# Node_Hub.net
KiCad netlist of a schematic drawn in Altium Designer
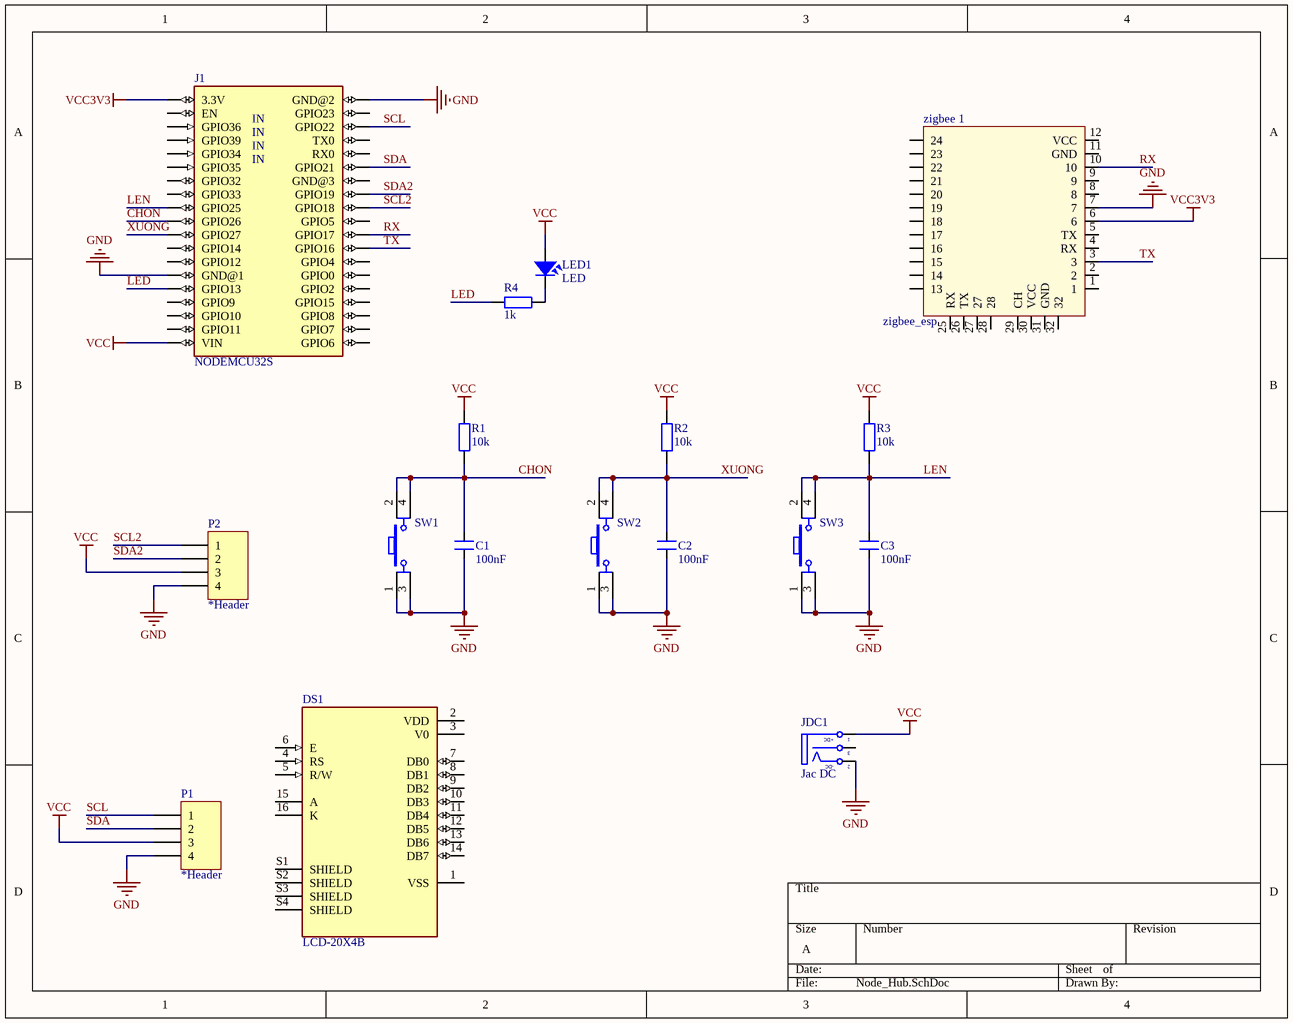
[diagram p0: Node_Hub.SchDoc]

(export (version "E")
  (design (tool "Eeschema 10.0.6"))
  (components
    (comp (ref "C1")
      (value "100nF")
      (footprint "CN1")
      (description "Cremic For Xtal 1pF => 100pF")
      (libsource (lib "syhaunguyen") (part "CN0"))
    )
    (comp (ref "C2")
      (value "100nF")
      (footprint "CN1")
      (description "Cremic For Xtal 1pF => 100pF")
      (libsource (lib "syhaunguyen") (part "CN0"))
    )
    (comp (ref "C3")
      (value "100nF")
      (footprint "CN1")
      (description "Cremic For Xtal 1pF => 100pF")
      (libsource (lib "syhaunguyen") (part "CN0"))
    )
    (comp (ref "DS1")
      (value "LCD-20X4B")
      (footprint "LCD_LCD-20X4B")
      (description "Display Development Tools 20X4 CHARACTER BLUE LCD W/BACKLIGHT")
      (fields (field (name "MF") "Gravitech"))
      (libsource (lib "LCD-20X4B") (part "LCD-20X4B"))
    )
    (comp (ref "J1")
      (value "NODEMCU32S")
      (footprint "NODEMCU32S")
      (description "WIFI MODULE V1")
      (fields (field (name "MF") "AI-Thinker") (field (name "MP") "NODEMCU-32S"))
      (libsource (lib "NODEMCU32S") (part "NODEMCU32S"))
    )
    (comp (ref "JDC1")
      (value "Jac DC")
      (footprint "DC-IN")
      (description "Jac DC input")
      (libsource (lib "syhaunguyen") (part "DCIN"))
    )
    (comp (ref "LED1")
      (value "LED")
      (footprint "LED-3")
      (description "LED Single colour Green and Red")
      (libsource (lib "syhaunguyen") (part "LED"))
    )
    (comp (ref "P1")
      (value "*Header")
      (footprint "HDR1X4")
      (description "Header, 4-Pin, Right Angle")
      (fields (field (name "PUBLISHER") "Altium Limited"))
      (libsource (lib "Cty1") (part "Header 4"))
    )
    (comp (ref "P2")
      (value "*Header")
      (footprint "HDR1X4")
      (description "Header, 4-Pin, Right Angle")
      (fields (field (name "PUBLISHER") "Altium Limited"))
      (libsource (lib "Cty1") (part "Header 4"))
    )
    (comp (ref "R1")
      (value "10k")
      (footprint "R1/4W")
      (description "Resistor 1/4W")
      (libsource (lib "syhaunguyen") (part "R1/4W"))
    )
    (comp (ref "R2")
      (value "10k")
      (footprint "R1/4W")
      (description "Resistor 1/4W")
      (libsource (lib "syhaunguyen") (part "R1/4W"))
    )
    (comp (ref "R3")
      (value "10k")
      (footprint "R1/4W")
      (description "Resistor 1/4W")
      (libsource (lib "syhaunguyen") (part "R1/4W"))
    )
    (comp (ref "R4")
      (value "1k")
      (footprint "R1/4W")
      (description "Resistor 1/4W")
      (libsource (lib "syhaunguyen") (part "R1/4W"))
    )
    (comp (ref "SW1")
      (value "SW")
      (footprint "SW4")
      (description "Switch button 4 pin")
      (libsource (lib "syhaunguyen") (part "SW4"))
    )
    (comp (ref "SW2")
      (value "SW")
      (footprint "SW4")
      (description "Switch button 4 pin")
      (libsource (lib "syhaunguyen") (part "SW4"))
    )
    (comp (ref "SW3")
      (value "SW")
      (footprint "SW4")
      (description "Switch button 4 pin")
      (libsource (lib "syhaunguyen") (part "SW4"))
    )
    (comp (ref "zigbee 1")
      (value "zigbee_esp")
      (footprint "zigbee")
      (libsource (lib "Main_stm8") (part "zigbee_esp"))
    )
  )
  (nets
    (net (code "2") (name "/CHON") (class "Default")
      (node (ref "C1") (pin "2") (pinfunction "2_2") (pintype "passive"))
      (node (ref "J1") (pin "GPIO26") (pinfunction "GPIO26_GPIO26") (pintype "bidirectional"))
      (node (ref "R1") (pin "1") (pinfunction "1_1") (pintype "passive"))
      (node (ref "SW1") (pin "2") (pintype "passive"))
      (node (ref "SW1") (pin "4") (pintype "passive"))
    )
    (net (code "3") (name "/LED") (class "Default")
      (node (ref "J1") (pin "GPIO13") (pinfunction "GPIO13_GPIO13") (pintype "bidirectional"))
      (node (ref "R4") (pin "1") (pinfunction "1_1") (pintype "passive"))
    )
    (net (code "4") (name "/LEN") (class "Default")
      (node (ref "C3") (pin "2") (pinfunction "2_2") (pintype "passive"))
      (node (ref "J1") (pin "GPIO25") (pinfunction "GPIO25_GPIO25") (pintype "bidirectional"))
      (node (ref "R3") (pin "1") (pinfunction "1_1") (pintype "passive"))
      (node (ref "SW3") (pin "2") (pintype "passive"))
      (node (ref "SW3") (pin "4") (pintype "passive"))
    )
    (net (code "5") (name "/RX") (class "Default")
      (node (ref "J1") (pin "GPIO17") (pinfunction "GPIO17_GPIO17") (pintype "bidirectional"))
      (node (ref "zigbee 1") (pin "10") (pinfunction "10_10") (pintype "passive"))
    )
    (net (code "6") (name "/SCL") (class "Default")
      (node (ref "J1") (pin "GPIO22") (pinfunction "GPIO22_GPIO22") (pintype "bidirectional"))
      (node (ref "P1") (pin "1") (pinfunction "1_1") (pintype "passive"))
    )
    (net (code "7") (name "/SCL2") (class "Default")
      (node (ref "J1") (pin "GPIO18") (pinfunction "GPIO18_GPIO18") (pintype "bidirectional"))
      (node (ref "P2") (pin "1") (pinfunction "1_1") (pintype "passive"))
    )
    (net (code "8") (name "/SDA") (class "Default")
      (node (ref "J1") (pin "GPIO21") (pinfunction "GPIO21_GPIO21") (pintype "bidirectional"))
      (node (ref "P1") (pin "2") (pinfunction "2_2") (pintype "passive"))
    )
    (net (code "9") (name "/SDA2") (class "Default")
      (node (ref "J1") (pin "GPIO19") (pinfunction "GPIO19_GPIO19") (pintype "bidirectional"))
      (node (ref "P2") (pin "2") (pinfunction "2_2") (pintype "passive"))
    )
    (net (code "10") (name "/TX") (class "Default")
      (node (ref "J1") (pin "GPIO16") (pinfunction "GPIO16_GPIO16") (pintype "bidirectional"))
      (node (ref "zigbee 1") (pin "3") (pinfunction "3_3") (pintype "passive"))
    )
    (net (code "11") (name "/XUONG") (class "Default")
      (node (ref "C2") (pin "2") (pinfunction "2_2") (pintype "passive"))
      (node (ref "J1") (pin "GPIO27") (pinfunction "GPIO27_GPIO27") (pintype "bidirectional"))
      (node (ref "R2") (pin "1") (pinfunction "1_1") (pintype "passive"))
      (node (ref "SW2") (pin "2") (pintype "passive"))
      (node (ref "SW2") (pin "4") (pintype "passive"))
    )
    (net (code "12") (name "GND") (class "Default")
      (node (ref "C1") (pin "1") (pinfunction "1_1") (pintype "passive"))
      (node (ref "C2") (pin "1") (pinfunction "1_1") (pintype "passive"))
      (node (ref "C3") (pin "1") (pinfunction "1_1") (pintype "passive"))
      (node (ref "J1") (pin "GND@1") (pinfunction "GND@1_GND@1") (pintype "bidirectional"))
      (node (ref "J1") (pin "GND@2") (pinfunction "GND@2_GND@2") (pintype "bidirectional"))
      (node (ref "JDC1") (pin "2") (pinfunction "TN_2") (pintype "passive"))
      (node (ref "P1") (pin "4") (pinfunction "4_4") (pintype "passive"))
      (node (ref "P2") (pin "4") (pinfunction "4_4") (pintype "passive"))
      (node (ref "SW1") (pin "1") (pintype "passive"))
      (node (ref "SW1") (pin "3") (pintype "passive"))
      (node (ref "SW2") (pin "1") (pintype "passive"))
      (node (ref "SW2") (pin "3") (pintype "passive"))
      (node (ref "SW3") (pin "1") (pintype "passive"))
      (node (ref "SW3") (pin "3") (pintype "passive"))
      (node (ref "zigbee 1") (pin "7") (pinfunction "7_7") (pintype "passive"))
    )
    (net (code "13") (name "Net-(LED1-Pad2)") (class "Default")
      (node (ref "LED1") (pin "2") (pinfunction "2_2") (pintype "passive"))
      (node (ref "R4") (pin "2") (pinfunction "2_2") (pintype "passive"))
    )
    (net (code "14") (name "VCC") (class "Default")
      (node (ref "J1") (pin "VIN") (pinfunction "VIN_VIN") (pintype "bidirectional"))
      (node (ref "JDC1") (pin "1") (pinfunction "T_1") (pintype "passive"))
      (node (ref "LED1") (pin "1") (pinfunction "1_1") (pintype "passive"))
      (node (ref "P1") (pin "3") (pinfunction "3_3") (pintype "passive"))
      (node (ref "P2") (pin "3") (pinfunction "3_3") (pintype "passive"))
      (node (ref "R1") (pin "2") (pinfunction "2_2") (pintype "passive"))
      (node (ref "R2") (pin "2") (pinfunction "2_2") (pintype "passive"))
      (node (ref "R3") (pin "2") (pinfunction "2_2") (pintype "passive"))
    )
    (net (code "15") (name "VCC3V3") (class "Default")
      (node (ref "J1") (pin "3V3") (pinfunction "3.3V_3V3") (pintype "bidirectional"))
      (node (ref "zigbee 1") (pin "6") (pinfunction "6_6") (pintype "passive"))
    )
    (net (code "16") (name "unconnected-(DS1-A-Pad15)") (class "Default")
      (node (ref "DS1") (pin "15") (pinfunction "A_15") (pintype "passive"))
    )
    (net (code "17") (name "unconnected-(DS1-DB0-Pad7)") (class "Default")
      (node (ref "DS1") (pin "7") (pinfunction "DB0_7") (pintype "bidirectional"))
    )
    (net (code "18") (name "unconnected-(DS1-DB1-Pad8)") (class "Default")
      (node (ref "DS1") (pin "8") (pinfunction "DB1_8") (pintype "bidirectional"))
    )
    (net (code "19") (name "unconnected-(DS1-DB2-Pad9)") (class "Default")
      (node (ref "DS1") (pin "9") (pinfunction "DB2_9") (pintype "bidirectional"))
    )
    (net (code "20") (name "unconnected-(DS1-DB3-Pad10)") (class "Default")
      (node (ref "DS1") (pin "10") (pinfunction "DB3_10") (pintype "bidirectional"))
    )
    (net (code "21") (name "unconnected-(DS1-DB4-Pad11)") (class "Default")
      (node (ref "DS1") (pin "11") (pinfunction "DB4_11") (pintype "bidirectional"))
    )
    (net (code "22") (name "unconnected-(DS1-DB5-Pad12)") (class "Default")
      (node (ref "DS1") (pin "12") (pinfunction "DB5_12") (pintype "bidirectional"))
    )
    (net (code "23") (name "unconnected-(DS1-DB6-Pad13)") (class "Default")
      (node (ref "DS1") (pin "13") (pinfunction "DB6_13") (pintype "bidirectional"))
    )
    (net (code "24") (name "unconnected-(DS1-DB7-Pad14)") (class "Default")
      (node (ref "DS1") (pin "14") (pinfunction "DB7_14") (pintype "bidirectional"))
    )
    (net (code "25") (name "unconnected-(DS1-E-Pad6)") (class "Default")
      (node (ref "DS1") (pin "6") (pinfunction "E_6") (pintype "input"))
    )
    (net (code "26") (name "unconnected-(DS1-K-Pad16)") (class "Default")
      (node (ref "DS1") (pin "16") (pinfunction "K_16") (pintype "passive"))
    )
    (net (code "27") (name "unconnected-(DS1-RS-Pad4)") (class "Default")
      (node (ref "DS1") (pin "4") (pinfunction "RS_4") (pintype "input"))
    )
    (net (code "28") (name "unconnected-(DS1-R{slash}W-Pad5)") (class "Default")
      (node (ref "DS1") (pin "5") (pinfunction "R/W_5") (pintype "input"))
    )
    (net (code "29") (name "unconnected-(DS1-SHIELD-PadS1)") (class "Default")
      (node (ref "DS1") (pin "S1") (pinfunction "SHIELD_S1") (pintype "passive"))
    )
    (net (code "30") (name "unconnected-(DS1-SHIELD-PadS2)") (class "Default")
      (node (ref "DS1") (pin "S2") (pinfunction "SHIELD_S2") (pintype "passive"))
    )
    (net (code "31") (name "unconnected-(DS1-SHIELD-PadS3)") (class "Default")
      (node (ref "DS1") (pin "S3") (pinfunction "SHIELD_S3") (pintype "passive"))
    )
    (net (code "32") (name "unconnected-(DS1-SHIELD-PadS4)") (class "Default")
      (node (ref "DS1") (pin "S4") (pinfunction "SHIELD_S4") (pintype "passive"))
    )
    (net (code "33") (name "unconnected-(DS1-V0-Pad3)") (class "Default")
      (node (ref "DS1") (pin "3") (pinfunction "V0_3") (pintype "power_in"))
    )
    (net (code "34") (name "unconnected-(DS1-VDD-Pad2)") (class "Default")
      (node (ref "DS1") (pin "2") (pinfunction "VDD_2") (pintype "power_in"))
    )
    (net (code "35") (name "unconnected-(DS1-VSS-Pad1)") (class "Default")
      (node (ref "DS1") (pin "1") (pinfunction "VSS_1") (pintype "power_in"))
    )
    (net (code "36") (name "unconnected-(J1-PadEN)") (class "Default")
      (node (ref "J1") (pin "EN") (pinfunction "EN_EN") (pintype "bidirectional"))
    )
    (net (code "37") (name "unconnected-(J1-PadGND@3)") (class "Default")
      (node (ref "J1") (pin "GND@3") (pinfunction "GND@3_GND@3") (pintype "bidirectional"))
    )
    (net (code "38") (name "unconnected-(J1-PadGPIO0)") (class "Default")
      (node (ref "J1") (pin "GPIO0") (pinfunction "GPIO0_GPIO0") (pintype "bidirectional"))
    )
    (net (code "39") (name "unconnected-(J1-PadGPIO2)") (class "Default")
      (node (ref "J1") (pin "GPIO2") (pinfunction "GPIO2_GPIO2") (pintype "bidirectional"))
    )
    (net (code "40") (name "unconnected-(J1-PadGPIO4)") (class "Default")
      (node (ref "J1") (pin "GPIO4") (pinfunction "GPIO4_GPIO4") (pintype "bidirectional"))
    )
    (net (code "41") (name "unconnected-(J1-PadGPIO5)") (class "Default")
      (node (ref "J1") (pin "GPIO5") (pinfunction "GPIO5_GPIO5") (pintype "bidirectional"))
    )
    (net (code "42") (name "unconnected-(J1-PadGPIO6)") (class "Default")
      (node (ref "J1") (pin "GPIO6") (pinfunction "GPIO6_GPIO6") (pintype "bidirectional"))
    )
    (net (code "43") (name "unconnected-(J1-PadGPIO7)") (class "Default")
      (node (ref "J1") (pin "GPIO7") (pinfunction "GPIO7_GPIO7") (pintype "bidirectional"))
    )
    (net (code "44") (name "unconnected-(J1-PadGPIO8)") (class "Default")
      (node (ref "J1") (pin "GPIO8") (pinfunction "GPIO8_GPIO8") (pintype "bidirectional"))
    )
    (net (code "45") (name "unconnected-(J1-PadGPIO9)") (class "Default")
      (node (ref "J1") (pin "GPIO9") (pinfunction "GPIO9_GPIO9") (pintype "bidirectional"))
    )
    (net (code "46") (name "unconnected-(J1-PadGPIO10)") (class "Default")
      (node (ref "J1") (pin "GPIO10") (pinfunction "GPIO10_GPIO10") (pintype "bidirectional"))
    )
    (net (code "47") (name "unconnected-(J1-PadGPIO11)") (class "Default")
      (node (ref "J1") (pin "GPIO11") (pinfunction "GPIO11_GPIO11") (pintype "bidirectional"))
    )
    (net (code "48") (name "unconnected-(J1-PadGPIO12)") (class "Default")
      (node (ref "J1") (pin "GPIO12") (pinfunction "GPIO12_GPIO12") (pintype "bidirectional"))
    )
    (net (code "49") (name "unconnected-(J1-PadGPIO14)") (class "Default")
      (node (ref "J1") (pin "GPIO14") (pinfunction "GPIO14_GPIO14") (pintype "bidirectional"))
    )
    (net (code "50") (name "unconnected-(J1-PadGPIO15)") (class "Default")
      (node (ref "J1") (pin "GPIO15") (pinfunction "GPIO15_GPIO15") (pintype "bidirectional"))
    )
    (net (code "51") (name "unconnected-(J1-PadGPIO23)") (class "Default")
      (node (ref "J1") (pin "GPIO23") (pinfunction "GPIO23_GPIO23") (pintype "bidirectional"))
    )
    (net (code "52") (name "unconnected-(J1-PadGPIO32)") (class "Default")
      (node (ref "J1") (pin "GPIO32") (pinfunction "GPIO32_GPIO32") (pintype "bidirectional"))
    )
    (net (code "53") (name "unconnected-(J1-PadGPIO33)") (class "Default")
      (node (ref "J1") (pin "GPIO33") (pinfunction "GPIO33_GPIO33") (pintype "bidirectional"))
    )
    (net (code "54") (name "unconnected-(J1-PadGPIO34)") (class "Default")
      (node (ref "J1") (pin "GPIO34") (pinfunction "GPIO34_GPIO34") (pintype "input"))
    )
    (net (code "55") (name "unconnected-(J1-PadGPIO35)") (class "Default")
      (node (ref "J1") (pin "GPIO35") (pinfunction "GPIO35_GPIO35") (pintype "input"))
    )
    (net (code "56") (name "unconnected-(J1-PadGPIO36)") (class "Default")
      (node (ref "J1") (pin "GPIO36") (pinfunction "GPIO36_GPIO36") (pintype "input"))
    )
    (net (code "57") (name "unconnected-(J1-PadGPIO39)") (class "Default")
      (node (ref "J1") (pin "GPIO39") (pinfunction "GPIO39_GPIO39") (pintype "input"))
    )
    (net (code "58") (name "unconnected-(J1-PadRX0)") (class "Default")
      (node (ref "J1") (pin "RX0") (pinfunction "RX0_RX0") (pintype "bidirectional"))
    )
    (net (code "59") (name "unconnected-(J1-PadTX0)") (class "Default")
      (node (ref "J1") (pin "TX0") (pinfunction "TX0_TX0") (pintype "bidirectional"))
    )
    (net (code "60") (name "unconnected-(JDC1-S-Pad3)") (class "Default")
      (node (ref "JDC1") (pin "3") (pinfunction "S_3") (pintype "power_in"))
    )
    (net (code "61") (name "unconnected-(zigbee 1-CH-Pad29)") (class "Default")
      (node (ref "zigbee 1") (pin "29") (pinfunction "CH_29") (pintype "passive"))
    )
    (net (code "62") (name "unconnected-(zigbee 1-GND-Pad11)") (class "Default")
      (node (ref "zigbee 1") (pin "11") (pinfunction "GND_11") (pintype "passive"))
    )
    (net (code "63") (name "unconnected-(zigbee 1-GND-Pad31)") (class "Default")
      (node (ref "zigbee 1") (pin "31") (pinfunction "GND_31") (pintype "passive"))
    )
    (net (code "64") (name "unconnected-(zigbee 1-Pad1)") (class "Default")
      (node (ref "zigbee 1") (pin "1") (pinfunction "1_1") (pintype "passive"))
    )
    (net (code "65") (name "unconnected-(zigbee 1-Pad2)") (class "Default")
      (node (ref "zigbee 1") (pin "2") (pinfunction "2_2") (pintype "passive"))
    )
    (net (code "66") (name "unconnected-(zigbee 1-Pad8)") (class "Default")
      (node (ref "zigbee 1") (pin "8") (pinfunction "8_8") (pintype "passive"))
    )
    (net (code "67") (name "unconnected-(zigbee 1-Pad9)") (class "Default")
      (node (ref "zigbee 1") (pin "9") (pinfunction "9_9") (pintype "passive"))
    )
    (net (code "68") (name "unconnected-(zigbee 1-Pad13)") (class "Default")
      (node (ref "zigbee 1") (pin "13") (pinfunction "13_13") (pintype "passive"))
    )
    (net (code "69") (name "unconnected-(zigbee 1-Pad14)") (class "Default")
      (node (ref "zigbee 1") (pin "14") (pinfunction "14_14") (pintype "passive"))
    )
    (net (code "70") (name "unconnected-(zigbee 1-Pad15)") (class "Default")
      (node (ref "zigbee 1") (pin "15") (pinfunction "15_15") (pintype "passive"))
    )
    (net (code "71") (name "unconnected-(zigbee 1-Pad16)") (class "Default")
      (node (ref "zigbee 1") (pin "16") (pinfunction "16_16") (pintype "passive"))
    )
    (net (code "72") (name "unconnected-(zigbee 1-Pad17)") (class "Default")
      (node (ref "zigbee 1") (pin "17") (pinfunction "17_17") (pintype "passive"))
    )
    (net (code "73") (name "unconnected-(zigbee 1-Pad18)") (class "Default")
      (node (ref "zigbee 1") (pin "18") (pinfunction "18_18") (pintype "passive"))
    )
    (net (code "74") (name "unconnected-(zigbee 1-Pad19)") (class "Default")
      (node (ref "zigbee 1") (pin "19") (pinfunction "19_19") (pintype "passive"))
    )
    (net (code "75") (name "unconnected-(zigbee 1-Pad20)") (class "Default")
      (node (ref "zigbee 1") (pin "20") (pinfunction "20_20") (pintype "passive"))
    )
    (net (code "76") (name "unconnected-(zigbee 1-Pad21)") (class "Default")
      (node (ref "zigbee 1") (pin "21") (pinfunction "21_21") (pintype "passive"))
    )
    (net (code "77") (name "unconnected-(zigbee 1-Pad22)") (class "Default")
      (node (ref "zigbee 1") (pin "22") (pinfunction "22_22") (pintype "passive"))
    )
    (net (code "78") (name "unconnected-(zigbee 1-Pad23)") (class "Default")
      (node (ref "zigbee 1") (pin "23") (pinfunction "23_23") (pintype "passive"))
    )
    (net (code "79") (name "unconnected-(zigbee 1-Pad24)") (class "Default")
      (node (ref "zigbee 1") (pin "24") (pinfunction "24_24") (pintype "passive"))
    )
    (net (code "80") (name "unconnected-(zigbee 1-Pad27)") (class "Default")
      (node (ref "zigbee 1") (pin "27") (pinfunction "27_27") (pintype "passive"))
    )
    (net (code "81") (name "unconnected-(zigbee 1-Pad28)") (class "Default")
      (node (ref "zigbee 1") (pin "28") (pinfunction "28_28") (pintype "passive"))
    )
    (net (code "82") (name "unconnected-(zigbee 1-Pad32)") (class "Default")
      (node (ref "zigbee 1") (pin "32") (pinfunction "32_32") (pintype "passive"))
    )
    (net (code "83") (name "unconnected-(zigbee 1-RX-Pad4)") (class "Default")
      (node (ref "zigbee 1") (pin "4") (pinfunction "RX_4") (pintype "passive"))
    )
    (net (code "84") (name "unconnected-(zigbee 1-RX-Pad25)") (class "Default")
      (node (ref "zigbee 1") (pin "25") (pinfunction "RX_25") (pintype "passive"))
    )
    (net (code "85") (name "unconnected-(zigbee 1-TX-Pad5)") (class "Default")
      (node (ref "zigbee 1") (pin "5") (pinfunction "TX_5") (pintype "passive"))
    )
    (net (code "86") (name "unconnected-(zigbee 1-TX-Pad26)") (class "Default")
      (node (ref "zigbee 1") (pin "26") (pinfunction "TX_26") (pintype "passive"))
    )
    (net (code "87") (name "unconnected-(zigbee 1-VCC-Pad12)") (class "Default")
      (node (ref "zigbee 1") (pin "12") (pinfunction "VCC_12") (pintype "passive"))
    )
    (net (code "88") (name "unconnected-(zigbee 1-VCC-Pad30)") (class "Default")
      (node (ref "zigbee 1") (pin "30") (pinfunction "VCC_30") (pintype "passive"))
    )
  )
)
